# source_eagle.net
KiCad netlist of a schematic drawn in EAGLE
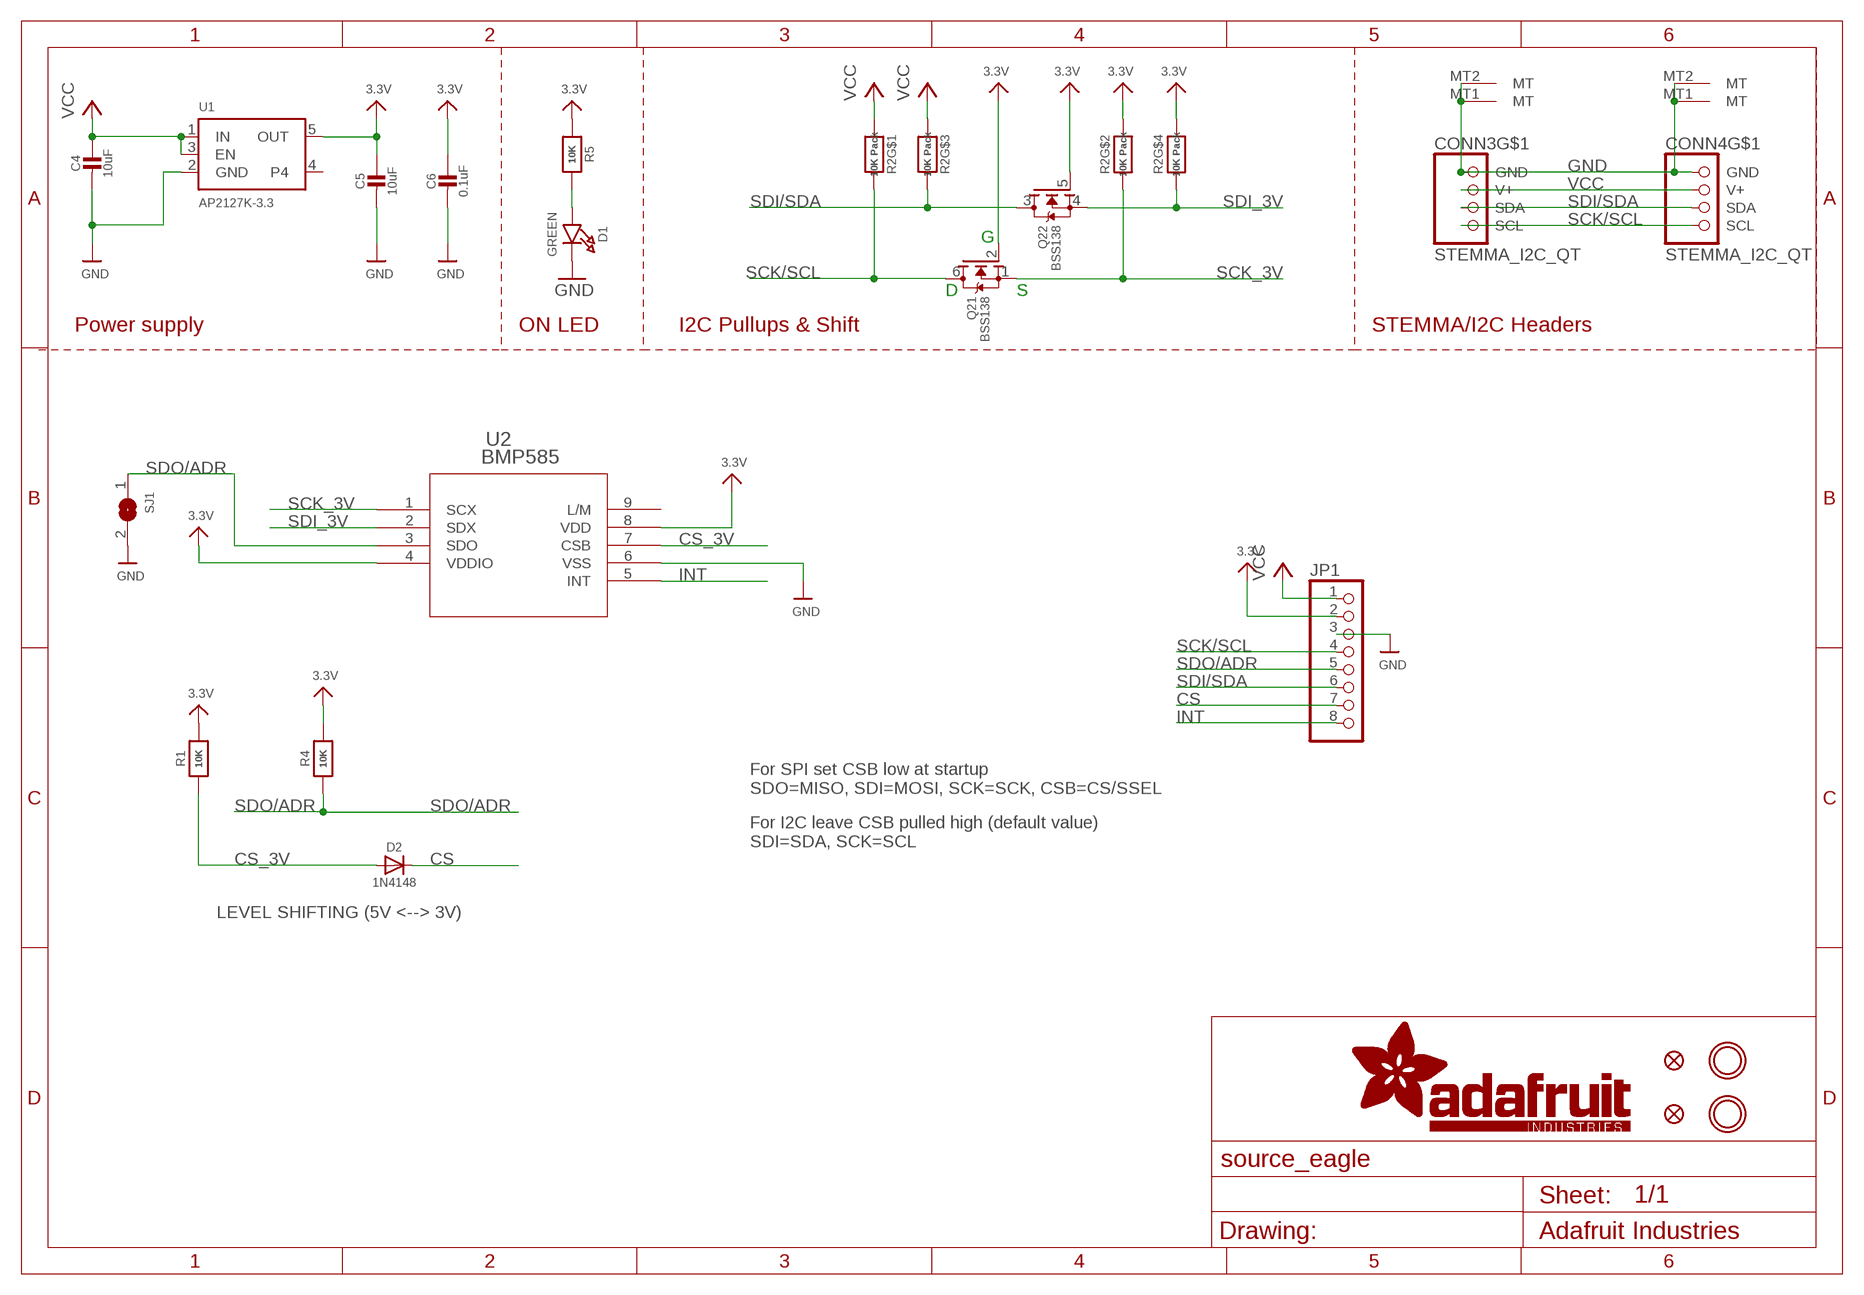
[diagram p0: schematic, sheet 1]

(export (version "E")
  (design (tool "Eeschema 10.0.6"))
  (components
    (comp (ref "C4")
      (value "10uF")
      (footprint "eagle-import:0805-NO")
      (libsource (lib "eagle-import") (part "CAP_CERAMIC0805-NOOUTLINE"))
    )
    (comp (ref "C5")
      (value "10uF")
      (footprint "eagle-import:0805-NO")
      (libsource (lib "eagle-import") (part "CAP_CERAMIC0805-NOOUTLINE"))
    )
    (comp (ref "C6")
      (value "0.1uF")
      (footprint "eagle-import:0603-NO")
      (libsource (lib "eagle-import") (part "CAP_CERAMIC0603_NO"))
    )
    (comp (ref "CONN3")
      (value "STEMMA_I2C_QT")
      (footprint "eagle-import:JST_SH4")
      (libsource (lib "eagle-import") (part "STEMMA_I2C_QT"))
    )
    (comp (ref "CONN4")
      (value "STEMMA_I2C_QT")
      (footprint "eagle-import:JST_SH4")
      (libsource (lib "eagle-import") (part "STEMMA_I2C_QT"))
    )
    (comp (ref "D1")
      (value "GREEN")
      (footprint "eagle-import:CHIPLED_0603_NOOUTLINE")
      (libsource (lib "eagle-import") (part "LED0603_NOOUTLINE"))
    )
    (comp (ref "D2")
      (value "1N4148")
      (footprint "eagle-import:SOD-323")
      (libsource (lib "eagle-import") (part "DIODESOD-323"))
    )
    (comp (ref "FID3")
      (value "FIDUCIAL_0.5MM")
      (footprint "eagle-import:FIDUCIAL_0.5MM")
      (libsource (lib "eagle-import") (part "FIDUCIAL_0.5MM"))
    )
    (comp (ref "FID4")
      (value "FIDUCIAL_0.5MM")
      (footprint "eagle-import:FIDUCIAL_0.5MM")
      (libsource (lib "eagle-import") (part "FIDUCIAL_0.5MM"))
    )
    (comp (ref "JP1")
      (value "HEADER-1X870MIL")
      (footprint "eagle-import:1X08_ROUND_70")
      (libsource (lib "eagle-import") (part "HEADER-1X870MIL"))
    )
    (comp (ref "Q2")
      (value "BSS138")
      (footprint "eagle-import:SOT363")
      (libsource (lib "eagle-import") (part "MOSFET-N_DUAL"))
    )
    (comp (ref "R1")
      (value "10K")
      (footprint "eagle-import:0603-NO")
      (libsource (lib "eagle-import") (part "RESISTOR_0603_NOOUT"))
    )
    (comp (ref "R2")
      (value "10K Pack")
      (footprint "eagle-import:RESPACK_4X0603")
      (libsource (lib "eagle-import") (part "RESISTOR_4PACK"))
    )
    (comp (ref "R4")
      (value "10K")
      (footprint "eagle-import:0603-NO")
      (libsource (lib "eagle-import") (part "RESISTOR_0603_NOOUT"))
    )
    (comp (ref "R5")
      (value "10K")
      (footprint "eagle-import:0603-NO")
      (libsource (lib "eagle-import") (part "RESISTOR_0603_NOOUT"))
    )
    (comp (ref "SJ1")
      (value "SOLDERJUMPER")
      (footprint "eagle-import:SOLDERJUMPER_ARROW_NOPASTE")
      (libsource (lib "eagle-import") (part "SOLDERJUMPER"))
    )
    (comp (ref "U$40")
      (value "MOUNTINGHOLE2.5")
      (footprint "eagle-import:MOUNTINGHOLE_2.5_PLATED")
      (libsource (lib "eagle-import") (part "MOUNTINGHOLE2.5"))
    )
    (comp (ref "U$41")
      (value "MOUNTINGHOLE2.5")
      (footprint "eagle-import:MOUNTINGHOLE_2.5_PLATED")
      (libsource (lib "eagle-import") (part "MOUNTINGHOLE2.5"))
    )
    (comp (ref "U1")
      (value "AP2127K-3.3")
      (footprint "eagle-import:SOT23-5")
      (libsource (lib "eagle-import") (part "VREG_SOT23-5"))
    )
    (comp (ref "U2")
      (value "BMP585")
      (footprint "eagle-import:LGA9_BMP585_BOS")
      (fields (field (name "COPYRIGHT") "Copyright (C) 2025 Ultra Librarian. All rights reserved."))
      (libsource (lib "eagle-import") (part "BMP585"))
    )
  )
  (nets
    (net (code "1") (name "/CS") (class "Default")
      (node (ref "D2") (pin "C") (pinfunction "C_C") (pintype "passive"))
      (node (ref "JP1") (pin "7") (pinfunction "7_7") (pintype "passive"))
    )
    (net (code "2") (name "/CS_3V") (class "Default")
      (node (ref "D2") (pin "A") (pinfunction "A_A") (pintype "passive"))
      (node (ref "R1") (pin "1") (pinfunction "1_1") (pintype "passive"))
      (node (ref "U2") (pin "7") (pinfunction "CSB_7") (pintype "input"))
    )
    (net (code "3") (name "/INT") (class "Default")
      (node (ref "JP1") (pin "8") (pinfunction "8_8") (pintype "passive"))
      (node (ref "U2") (pin "5") (pinfunction "INT_5") (pintype "output"))
    )
    (net (code "4") (name "/SCK_3V") (class "Default")
      (node (ref "Q2") (pin "1") (pinfunction "S_1") (pintype "bidirectional"))
      (node (ref "R2") (pin "7") (pinfunction "2_7") (pintype "passive"))
      (node (ref "U2") (pin "1") (pinfunction "SCX_1") (pintype "input"))
    )
    (net (code "5") (name "/SCK{slash}SCL") (class "Default")
      (node (ref "CONN3") (pin "4") (pinfunction "SCL_4") (pintype "passive"))
      (node (ref "CONN4") (pin "4") (pinfunction "SCL_4") (pintype "passive"))
      (node (ref "JP1") (pin "4") (pinfunction "4_4") (pintype "passive"))
      (node (ref "Q2") (pin "6") (pinfunction "D_6") (pintype "bidirectional"))
      (node (ref "R2") (pin "8") (pinfunction "2_8") (pintype "passive"))
    )
    (net (code "6") (name "/SDI_3V") (class "Default")
      (node (ref "Q2") (pin "4") (pinfunction "S_4") (pintype "bidirectional"))
      (node (ref "R2") (pin "5") (pinfunction "2_5") (pintype "passive"))
      (node (ref "U2") (pin "2") (pinfunction "SDX_2") (pintype "bidirectional"))
    )
    (net (code "7") (name "/SDI{slash}SDA") (class "Default")
      (node (ref "CONN3") (pin "3") (pinfunction "SDA_3") (pintype "passive"))
      (node (ref "CONN4") (pin "3") (pinfunction "SDA_3") (pintype "passive"))
      (node (ref "JP1") (pin "6") (pinfunction "6_6") (pintype "passive"))
      (node (ref "Q2") (pin "3") (pinfunction "D_3") (pintype "bidirectional"))
      (node (ref "R2") (pin "6") (pinfunction "2_6") (pintype "passive"))
    )
    (net (code "8") (name "/SDO{slash}ADR") (class "Default")
      (node (ref "JP1") (pin "5") (pinfunction "5_5") (pintype "passive"))
      (node (ref "R4") (pin "1") (pinfunction "1_1") (pintype "passive"))
      (node (ref "SJ1") (pin "1") (pinfunction "1_1") (pintype "passive"))
      (node (ref "U2") (pin "3") (pinfunction "SDO_3") (pintype "bidirectional"))
    )
    (net (code "9") (name "3.3V") (class "Default")
      (node (ref "C5") (pin "1") (pinfunction "1_1") (pintype "passive"))
      (node (ref "C6") (pin "1") (pinfunction "1_1") (pintype "passive"))
      (node (ref "JP1") (pin "2") (pinfunction "2_2") (pintype "passive"))
      (node (ref "Q2") (pin "2") (pinfunction "G_2") (pintype "bidirectional"))
      (node (ref "Q2") (pin "5") (pinfunction "G_5") (pintype "bidirectional"))
      (node (ref "R1") (pin "2") (pinfunction "2_2") (pintype "passive"))
      (node (ref "R2") (pin "2") (pinfunction "1_2") (pintype "passive"))
      (node (ref "R2") (pin "4") (pinfunction "1_4") (pintype "passive"))
      (node (ref "R4") (pin "2") (pinfunction "2_2") (pintype "passive"))
      (node (ref "R5") (pin "1") (pinfunction "1_1") (pintype "passive"))
      (node (ref "U1") (pin "5") (pinfunction "OUT_5") (pintype "power_in"))
      (node (ref "U2") (pin "4") (pinfunction "VDDIO_4") (pintype "power_in"))
      (node (ref "U2") (pin "8") (pinfunction "VDD_8") (pintype "power_in"))
    )
    (net (code "10") (name "GND") (class "Default")
      (node (ref "C4") (pin "2") (pinfunction "2_2") (pintype "passive"))
      (node (ref "C5") (pin "2") (pinfunction "2_2") (pintype "passive"))
      (node (ref "C6") (pin "2") (pinfunction "2_2") (pintype "passive"))
      (node (ref "CONN3") (pin "1") (pinfunction "GND_1") (pintype "passive"))
      (node (ref "CONN3") (pin "MT1") (pinfunction "MT_MT1") (pintype "bidirectional"))
      (node (ref "CONN3") (pin "MT2") (pinfunction "MT_MT2") (pintype "bidirectional"))
      (node (ref "CONN4") (pin "1") (pinfunction "GND_1") (pintype "passive"))
      (node (ref "CONN4") (pin "MT1") (pinfunction "MT_MT1") (pintype "bidirectional"))
      (node (ref "CONN4") (pin "MT2") (pinfunction "MT_MT2") (pintype "bidirectional"))
      (node (ref "D1") (pin "C") (pinfunction "C_C") (pintype "passive"))
      (node (ref "JP1") (pin "3") (pinfunction "3_3") (pintype "passive"))
      (node (ref "SJ1") (pin "2") (pinfunction "2_2") (pintype "passive"))
      (node (ref "U1") (pin "2") (pinfunction "GND_2") (pintype "power_in"))
      (node (ref "U2") (pin "6") (pinfunction "VSS_6") (pintype "passive"))
    )
    (net (code "11") (name "Net-(D1-PadA)") (class "Default")
      (node (ref "D1") (pin "A") (pinfunction "A_A") (pintype "passive"))
      (node (ref "R5") (pin "2") (pinfunction "2_2") (pintype "passive"))
    )
    (net (code "12") (name "VCC") (class "Default")
      (node (ref "C4") (pin "1") (pinfunction "1_1") (pintype "passive"))
      (node (ref "CONN3") (pin "2") (pinfunction "V+_2") (pintype "passive"))
      (node (ref "CONN4") (pin "2") (pinfunction "V+_2") (pintype "passive"))
      (node (ref "JP1") (pin "1") (pinfunction "1_1") (pintype "passive"))
      (node (ref "R2") (pin "1") (pinfunction "1_1") (pintype "passive"))
      (node (ref "R2") (pin "3") (pinfunction "1_3") (pintype "passive"))
      (node (ref "U1") (pin "1") (pinfunction "IN_1") (pintype "power_in"))
      (node (ref "U1") (pin "3") (pinfunction "EN_3") (pintype "input"))
    )
    (net (code "13") (name "unconnected-(U1-P4-Pad4)") (class "Default")
      (node (ref "U1") (pin "4") (pinfunction "P4_4") (pintype "bidirectional"))
    )
    (net (code "14") (name "unconnected-(U2-L{slash}M-Pad9)") (class "Default")
      (node (ref "U2") (pin "9") (pinfunction "L/M_9") (pintype "no_connect"))
    )
  )
)
